# ok-wake.net
KiCad netlist of a schematic drawn in EAGLE
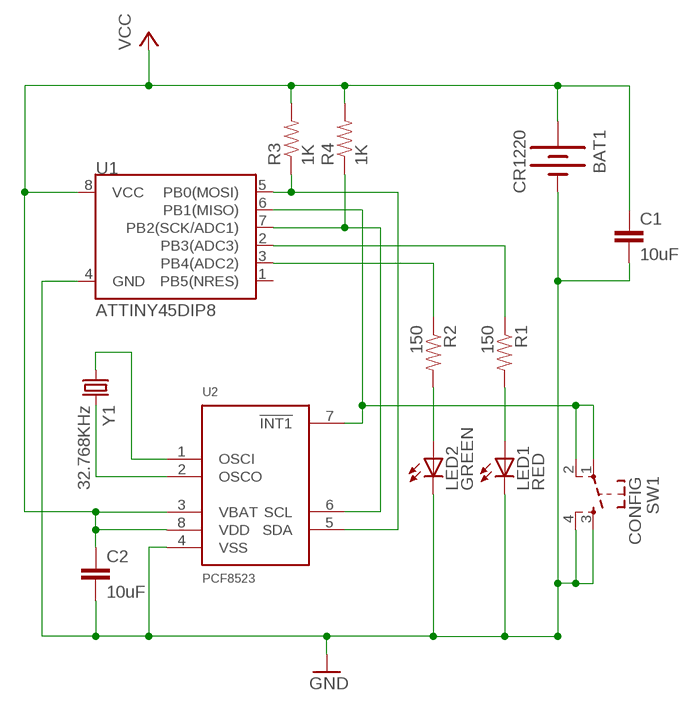
[diagram p0: schematic, sheet 1]

(export (version "E")
  (design (tool "Eeschema 10.0.6"))
  (components
    (comp (ref "BAT1")
      (value "CR1220")
      (footprint "eagle-import:BATTCON_12MM")
      (libsource (lib "eagle-import") (part "BATTERY12MM"))
    )
    (comp (ref "C1")
      (value "10uF")
      (footprint "eagle-import:1206")
      (libsource (lib "eagle-import") (part "CAP1206"))
    )
    (comp (ref "C2")
      (value "10uF")
      (footprint "eagle-import:1206")
      (libsource (lib "eagle-import") (part "CAP1206"))
    )
    (comp (ref "LED1")
      (value "RED")
      (footprint "eagle-import:CHIP-LED0805")
      (libsource (lib "eagle-import") (part "LEDCHIP-LED0805"))
    )
    (comp (ref "LED2")
      (value "GREEN")
      (footprint "eagle-import:CHIP-LED0805")
      (libsource (lib "eagle-import") (part "LEDCHIP-LED0805"))
    )
    (comp (ref "R1")
      (value "150")
      (footprint "eagle-import:0805")
      (libsource (lib "eagle-import") (part "RESISTOR0805-RES"))
    )
    (comp (ref "R2")
      (value "150")
      (footprint "eagle-import:0805")
      (libsource (lib "eagle-import") (part "RESISTOR0805-RES"))
    )
    (comp (ref "R3")
      (value "1K")
      (footprint "eagle-import:0805")
      (libsource (lib "eagle-import") (part "RESISTOR0805-RES"))
    )
    (comp (ref "R4")
      (value "1K")
      (footprint "eagle-import:0805")
      (libsource (lib "eagle-import") (part "RESISTOR0805-RES"))
    )
    (comp (ref "SW1")
      (value "CONFIG")
      (footprint "eagle-import:SW_TACT_SMALL")
      (libsource (lib "eagle-import") (part "SW_TACT"))
    )
    (comp (ref "U1")
      (value "ATTINY45DIP8")
      (footprint "eagle-import:DIP08")
      (libsource (lib "eagle-import") (part "ATTINY45DIP8"))
    )
    (comp (ref "U2")
      (value "PCF8523")
      (footprint "eagle-import:SO8")
      (libsource (lib "eagle-import") (part "PCF8523"))
    )
    (comp (ref "Y1")
      (value "32.768KHz")
      (footprint "eagle-import:CRYSTAL-32KHZ-SMD")
      (libsource (lib "eagle-import") (part "CRYSTAL32-SMD"))
    )
  )
  (nets
    (net (code "1") (name "GND") (class "Default")
      (node (ref "BAT1") (pin "GND") (pinfunction "-_GND") (pintype "power_in"))
      (node (ref "C1") (pin "2") (pinfunction "2_2") (pintype "passive"))
      (node (ref "C2") (pin "2") (pinfunction "2_2") (pintype "passive"))
      (node (ref "LED1") (pin "C") (pinfunction "C_C") (pintype "passive"))
      (node (ref "LED2") (pin "C") (pinfunction "C_C") (pintype "passive"))
      (node (ref "SW1") (pin "3") (pinfunction "3_3") (pintype "passive"))
      (node (ref "SW1") (pin "4") (pinfunction "4_4") (pintype "passive"))
      (node (ref "U1") (pin "4") (pinfunction "GND_4") (pintype "bidirectional"))
      (node (ref "U2") (pin "4") (pinfunction "VSS_4") (pintype "power_in"))
    )
    (net (code "2") (name "Net-(LED1-PadA)") (class "Default")
      (node (ref "LED1") (pin "A") (pinfunction "A_A") (pintype "passive"))
      (node (ref "R1") (pin "2") (pinfunction "2_2") (pintype "passive"))
    )
    (net (code "3") (name "Net-(LED2-PadA)") (class "Default")
      (node (ref "LED2") (pin "A") (pinfunction "A_A") (pintype "passive"))
      (node (ref "R2") (pin "2") (pinfunction "2_2") (pintype "passive"))
    )
    (net (code "4") (name "Net-(U1-PB0(MOSI))") (class "Default")
      (node (ref "R3") (pin "1") (pinfunction "1_1") (pintype "passive"))
      (node (ref "U1") (pin "5") (pinfunction "PB0(MOSI)_5") (pintype "bidirectional"))
      (node (ref "U2") (pin "5") (pinfunction "SDA_5") (pintype "bidirectional"))
    )
    (net (code "5") (name "Net-(U1-PB1(MISO))") (class "Default")
      (node (ref "SW1") (pin "1") (pinfunction "1_1") (pintype "passive"))
      (node (ref "SW1") (pin "2") (pinfunction "2_2") (pintype "passive"))
      (node (ref "U1") (pin "6") (pinfunction "PB1(MISO)_6") (pintype "bidirectional"))
      (node (ref "U2") (pin "7") (pinfunction "~{INT1}_7") (pintype "output"))
    )
    (net (code "6") (name "Net-(U1-PB2(SCK{slash}ADC1))") (class "Default")
      (node (ref "R4") (pin "1") (pinfunction "1_1") (pintype "passive"))
      (node (ref "U1") (pin "7") (pinfunction "PB2(SCK/ADC1)_7") (pintype "bidirectional"))
      (node (ref "U2") (pin "6") (pinfunction "SCL_6") (pintype "input"))
    )
    (net (code "7") (name "Net-(U1-PB3(ADC3))") (class "Default")
      (node (ref "R1") (pin "1") (pinfunction "1_1") (pintype "passive"))
      (node (ref "U1") (pin "2") (pinfunction "PB3(ADC3)_2") (pintype "bidirectional"))
    )
    (net (code "8") (name "Net-(U1-PB4(ADC2))") (class "Default")
      (node (ref "R2") (pin "1") (pinfunction "1_1") (pintype "passive"))
      (node (ref "U1") (pin "3") (pinfunction "PB4(ADC2)_3") (pintype "bidirectional"))
    )
    (net (code "9") (name "Net-(U2-OSCI)") (class "Default")
      (node (ref "U2") (pin "1") (pinfunction "OSCI_1") (pintype "input"))
      (node (ref "Y1") (pin "X1") (pinfunction "1_X1") (pintype "passive"))
    )
    (net (code "10") (name "Net-(U2-OSCO)") (class "Default")
      (node (ref "U2") (pin "2") (pinfunction "OSCO_2") (pintype "output"))
      (node (ref "Y1") (pin "X2") (pinfunction "2_X2") (pintype "passive"))
    )
    (net (code "11") (name "VCC") (class "Default")
      (node (ref "BAT1") (pin "PWR@1") (pinfunction "+_PWR@1") (pintype "power_in"))
      (node (ref "C1") (pin "1") (pinfunction "1_1") (pintype "passive"))
      (node (ref "C2") (pin "1") (pinfunction "1_1") (pintype "passive"))
      (node (ref "R3") (pin "2") (pinfunction "2_2") (pintype "passive"))
      (node (ref "R4") (pin "2") (pinfunction "2_2") (pintype "passive"))
      (node (ref "U1") (pin "8") (pinfunction "VCC_8") (pintype "bidirectional"))
      (node (ref "U2") (pin "3") (pinfunction "VBAT_3") (pintype "power_in"))
      (node (ref "U2") (pin "8") (pinfunction "VDD_8") (pintype "power_in"))
    )
    (net (code "12") (name "unconnected-(U1-PB5(NRES)-Pad1)") (class "Default")
      (node (ref "U1") (pin "1") (pinfunction "PB5(NRES)_1") (pintype "bidirectional"))
    )
  )
)
